# RightSide.net
KiCad netlist of a schematic drawn in Altium Designer
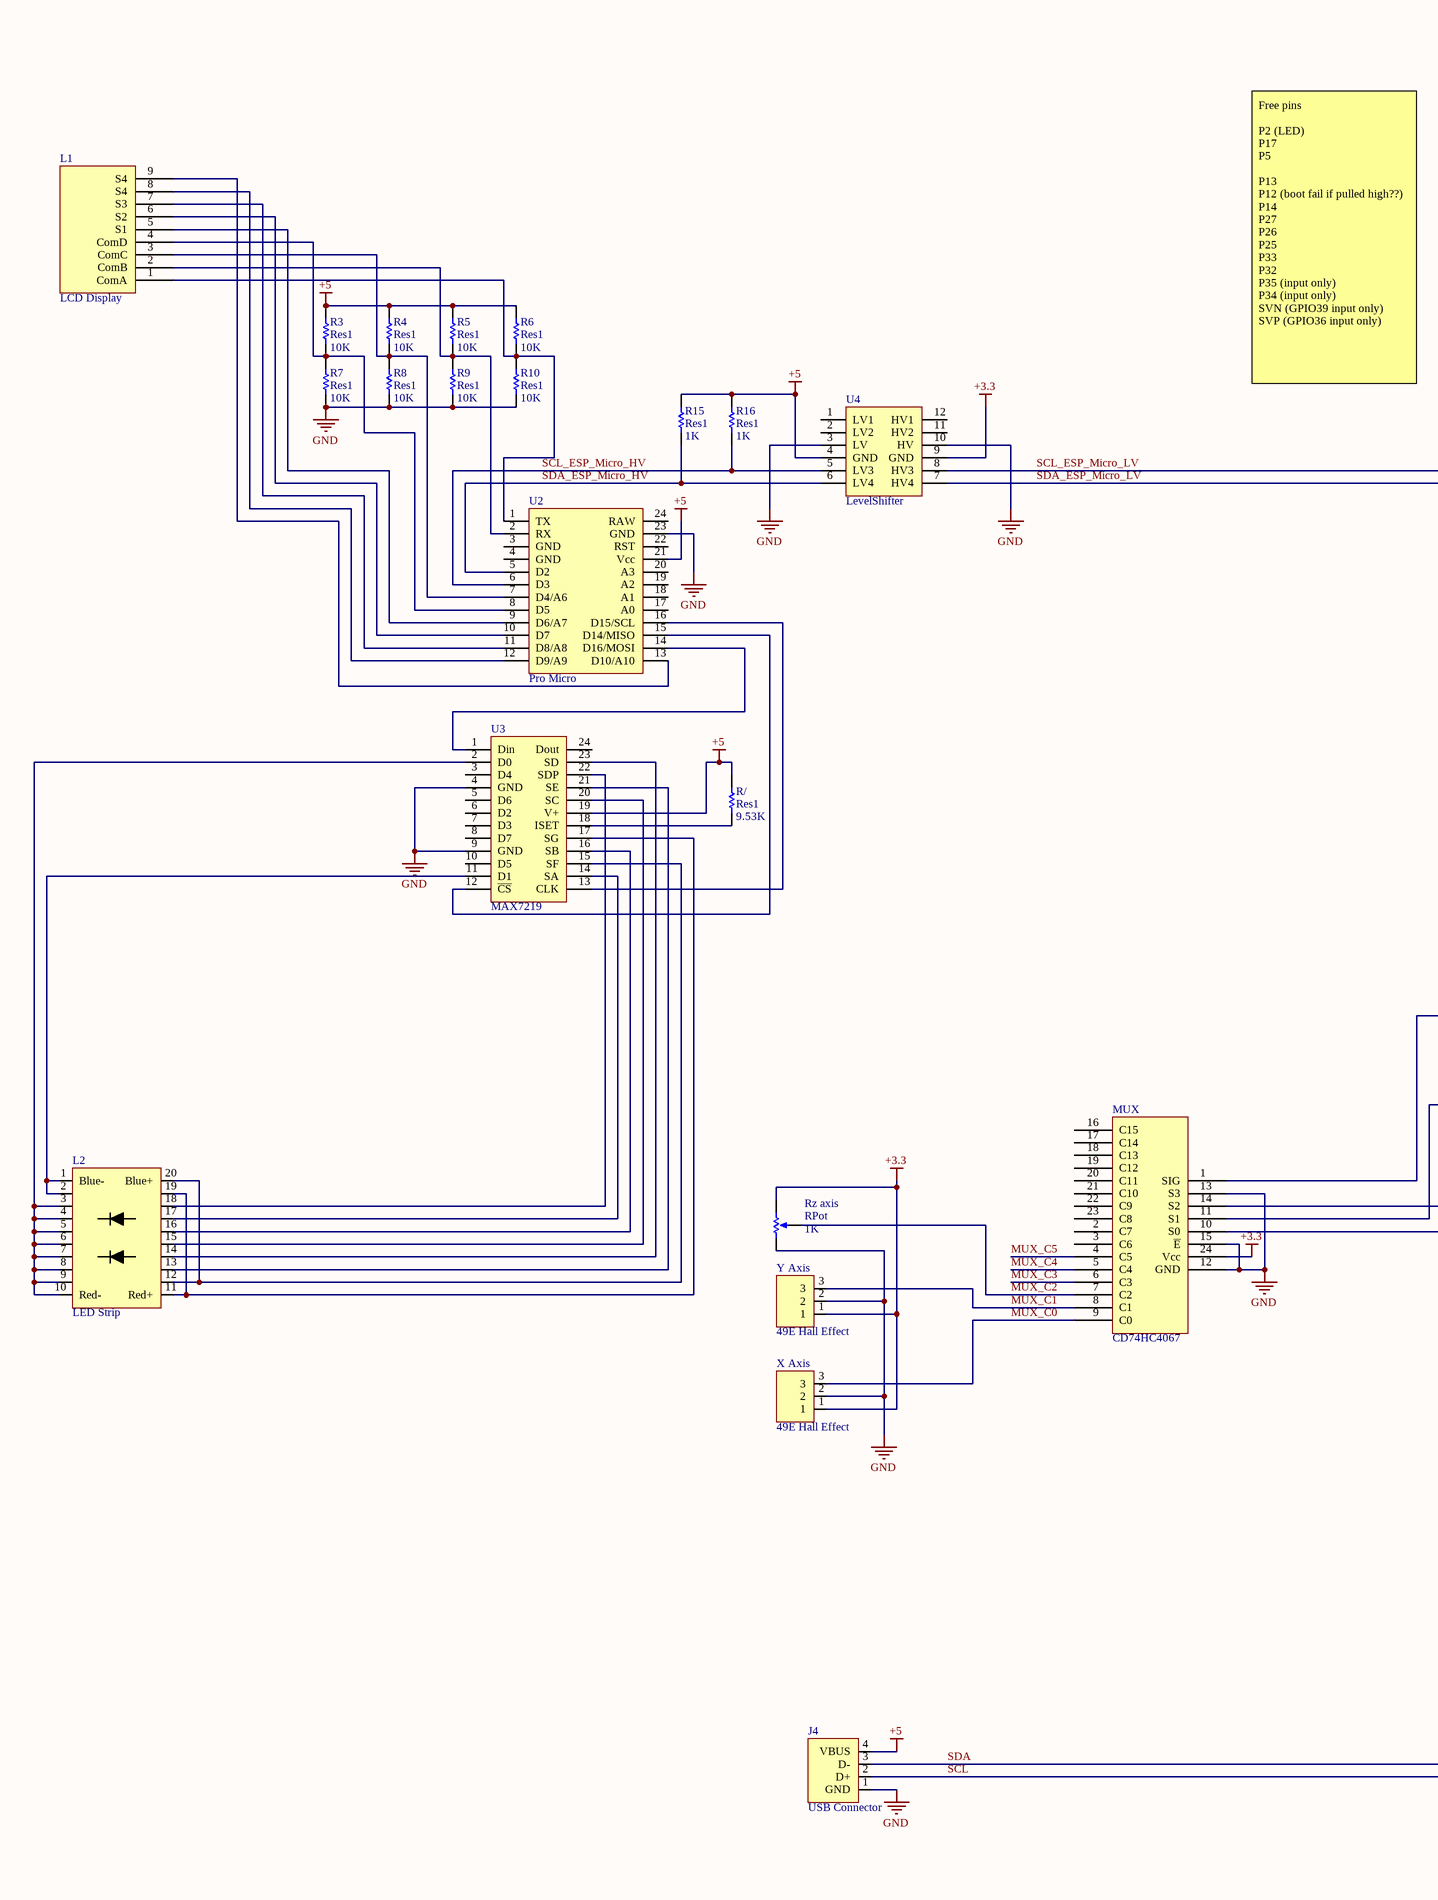
[diagram p0: RightSide.SchDoc, left]
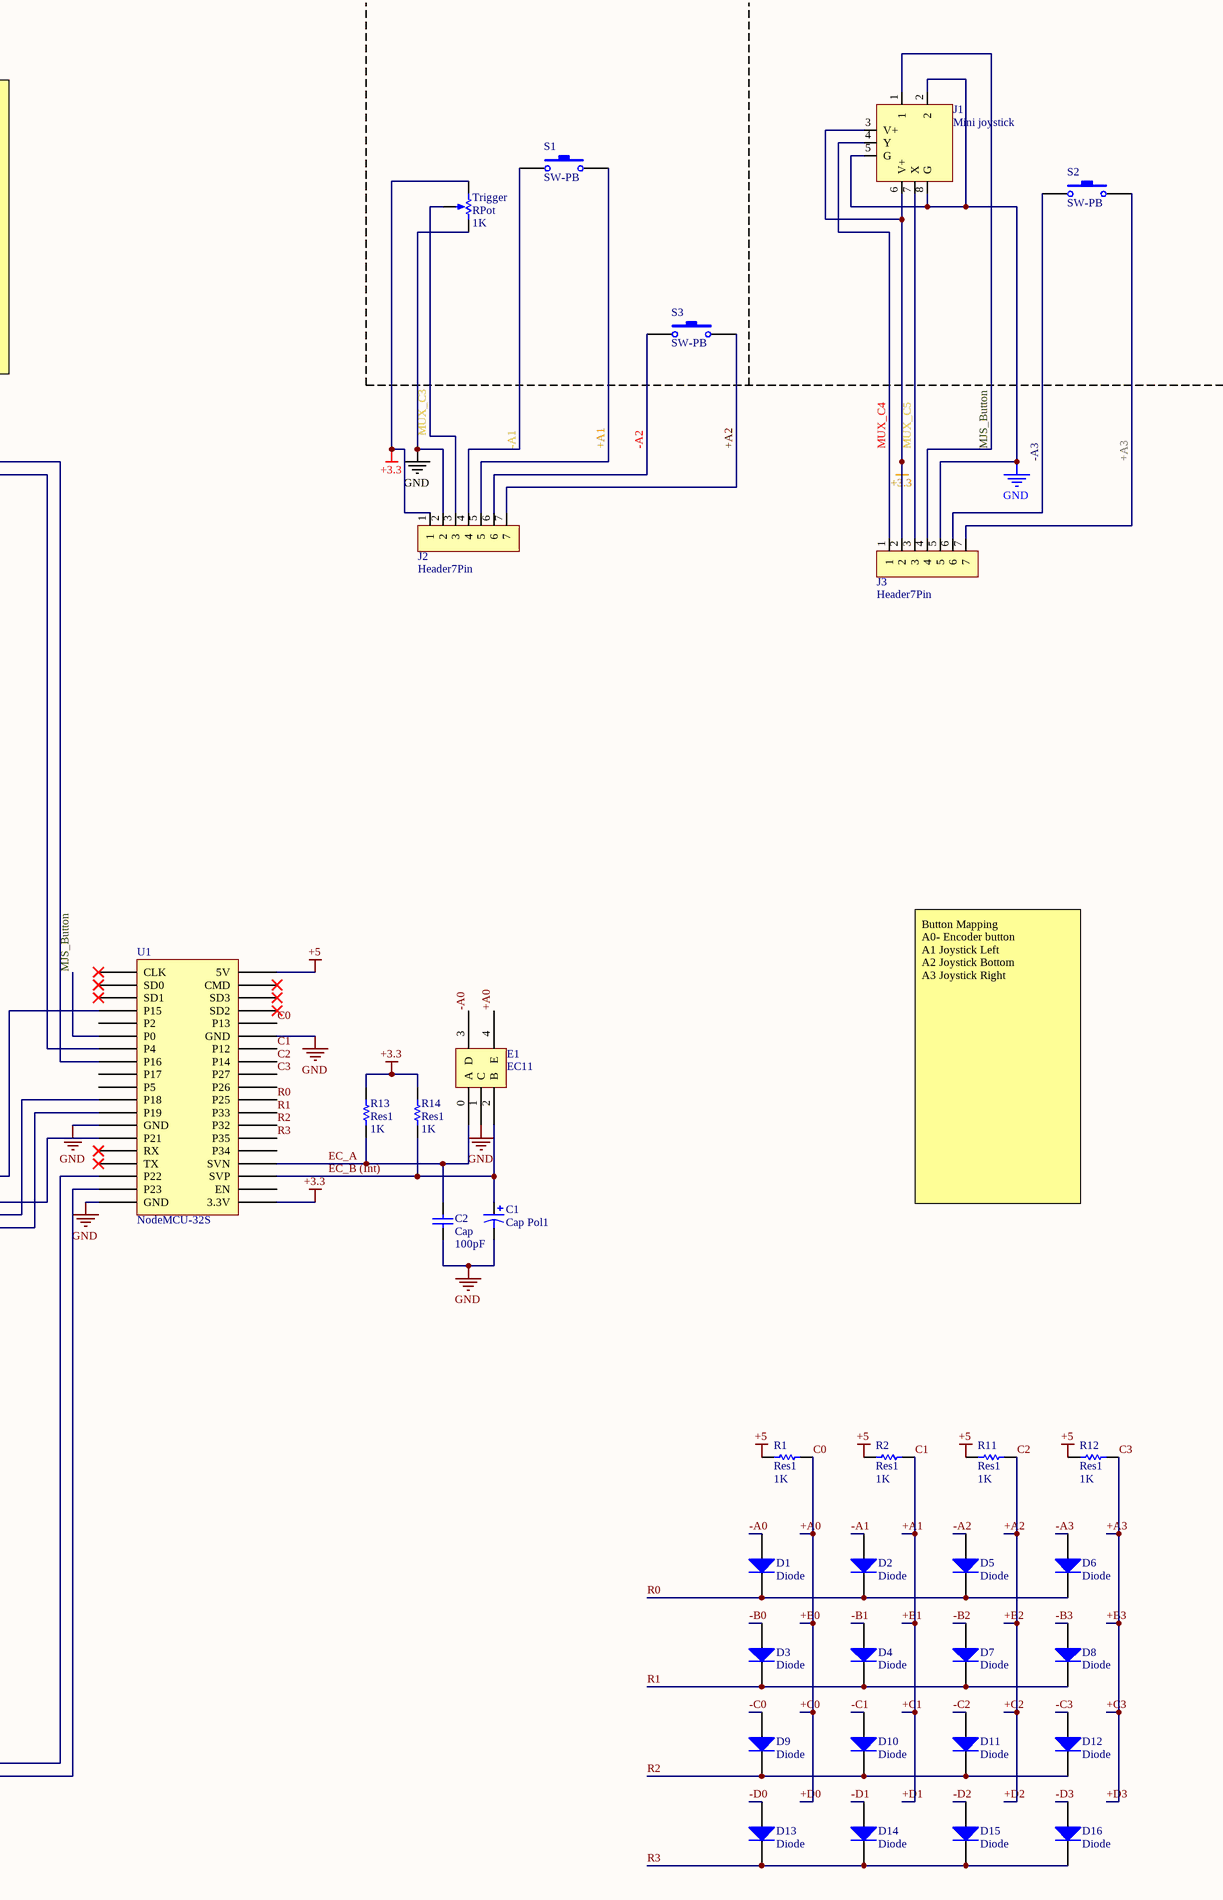
[diagram p1: RightSide.SchDoc, right]

(export (version "E")
  (design (tool "Eeschema 10.0.6"))
  (components
    (comp (ref "C1")
      (value "Cap Pol1")
      (footprint "RB7.6-15")
      (description "Polarized Capacitor (Radial)")
      (fields (field (name "PUBLISHER") "Altium Limited"))
      (libsource (lib "Miscellaneous Devices") (part "Cap Pol1"))
    )
    (comp (ref "C2")
      (value "Cap")
      (footprint "RAD-0.3")
      (description "Capacitor")
      (fields (field (name "ALTIUM_VALUE") "100pF") (field (name "PUBLISHER") "Altium Limited"))
      (libsource (lib "Miscellaneous Devices") (part "Cap"))
    )
    (comp (ref "D1")
      (value "Diode")
      (footprint "Diode_300mil")
      (description "Default Diode")
      (fields (field (name "PUBLISHER") "Altium Limited"))
      (libsource (lib "Miscellaneous Devices") (part "Diode"))
    )
    (comp (ref "D2")
      (value "Diode")
      (footprint "Diode_300mil")
      (description "Default Diode")
      (fields (field (name "PUBLISHER") "Altium Limited"))
      (libsource (lib "Miscellaneous Devices") (part "Diode"))
    )
    (comp (ref "D3")
      (value "Diode")
      (footprint "Diode_300mil")
      (description "Default Diode")
      (fields (field (name "PUBLISHER") "Altium Limited"))
      (libsource (lib "Miscellaneous Devices") (part "Diode"))
    )
    (comp (ref "D4")
      (value "Diode")
      (footprint "Diode_300mil")
      (description "Default Diode")
      (fields (field (name "PUBLISHER") "Altium Limited"))
      (libsource (lib "Miscellaneous Devices") (part "Diode"))
    )
    (comp (ref "D5")
      (value "Diode")
      (footprint "Diode_300mil")
      (description "Default Diode")
      (fields (field (name "PUBLISHER") "Altium Limited"))
      (libsource (lib "Miscellaneous Devices") (part "Diode"))
    )
    (comp (ref "D6")
      (value "Diode")
      (footprint "Diode_300mil")
      (description "Default Diode")
      (fields (field (name "PUBLISHER") "Altium Limited"))
      (libsource (lib "Miscellaneous Devices") (part "Diode"))
    )
    (comp (ref "D7")
      (value "Diode")
      (footprint "Diode_300mil")
      (description "Default Diode")
      (fields (field (name "PUBLISHER") "Altium Limited"))
      (libsource (lib "Miscellaneous Devices") (part "Diode"))
    )
    (comp (ref "D8")
      (value "Diode")
      (footprint "Diode_300mil")
      (description "Default Diode")
      (fields (field (name "PUBLISHER") "Altium Limited"))
      (libsource (lib "Miscellaneous Devices") (part "Diode"))
    )
    (comp (ref "D9")
      (value "Diode")
      (footprint "Diode_300mil")
      (description "Default Diode")
      (fields (field (name "PUBLISHER") "Altium Limited"))
      (libsource (lib "Miscellaneous Devices") (part "Diode"))
    )
    (comp (ref "D10")
      (value "Diode")
      (footprint "Diode_300mil")
      (description "Default Diode")
      (fields (field (name "PUBLISHER") "Altium Limited"))
      (libsource (lib "Miscellaneous Devices") (part "Diode"))
    )
    (comp (ref "D11")
      (value "Diode")
      (footprint "Diode_300mil")
      (description "Default Diode")
      (fields (field (name "PUBLISHER") "Altium Limited"))
      (libsource (lib "Miscellaneous Devices") (part "Diode"))
    )
    (comp (ref "D12")
      (value "Diode")
      (footprint "Diode_300mil")
      (description "Default Diode")
      (fields (field (name "PUBLISHER") "Altium Limited"))
      (libsource (lib "Miscellaneous Devices") (part "Diode"))
    )
    (comp (ref "D13")
      (value "Diode")
      (footprint "Diode_300mil")
      (description "Default Diode")
      (fields (field (name "PUBLISHER") "Altium Limited"))
      (libsource (lib "Miscellaneous Devices") (part "Diode"))
    )
    (comp (ref "D14")
      (value "Diode")
      (footprint "Diode_300mil")
      (description "Default Diode")
      (fields (field (name "PUBLISHER") "Altium Limited"))
      (libsource (lib "Miscellaneous Devices") (part "Diode"))
    )
    (comp (ref "D15")
      (value "Diode")
      (footprint "Diode_300mil")
      (description "Default Diode")
      (fields (field (name "PUBLISHER") "Altium Limited"))
      (libsource (lib "Miscellaneous Devices") (part "Diode"))
    )
    (comp (ref "D16")
      (value "Diode")
      (footprint "Diode_300mil")
      (description "Default Diode")
      (fields (field (name "PUBLISHER") "Altium Limited"))
      (libsource (lib "Miscellaneous Devices") (part "Diode"))
    )
    (comp (ref "E1")
      (value "EC11")
      (footprint "Encoder")
      (description "Rot Encoder\r\nC GND\r\nPull up A,B")
      (libsource (lib "PartsSchLib") (part "EC11"))
    )
    (comp (ref "J1")
      (value "Mini joystick")
      (footprint "MiniJoyStick")
      (libsource (lib "PartsSchLib") (part "Mini joystick"))
    )
    (comp (ref "J2")
      (value "Header7Pin")
      (footprint "Header7Pin")
      (libsource (lib "PartsSchLib") (part "Header7Pin"))
    )
    (comp (ref "J3")
      (value "Header7Pin")
      (footprint "Header7Pin")
      (libsource (lib "PartsSchLib") (part "Header7Pin"))
    )
    (comp (ref "J4")
      (value "USB Connector")
      (footprint "USB-B")
      (libsource (lib "PartsSchLib") (part "USB Connector"))
    )
    (comp (ref "L1")
      (value "LCD Display")
      (footprint "LCD Display")
      (libsource (lib "PartsSchLib") (part "LCD Display"))
    )
    (comp (ref "L2") (value "LED Strip") (libsource (lib "PartsSchLib") (part "LED Strip")))
    (comp (ref "MUX")
      (value "CD74HC4067")
      (footprint "CD74HC4067")
      (description "Analog Multiplexer")
      (libsource (lib "PartsSchLib") (part "CD74HC4067"))
    )
    (comp (ref "R/")
      (value "Res1")
      (footprint "AXIAL-0.3")
      (description "Resistor")
      (fields (field (name "ALTIUM_VALUE") "9.53K") (field (name "PUBLISHER") "Altium Limited"))
      (libsource (lib "Miscellaneous Devices") (part "Res1"))
    )
    (comp (ref "R1")
      (value "Res1")
      (footprint "AXIAL-0.3")
      (description "Resistor")
      (fields (field (name "ALTIUM_VALUE") "1K") (field (name "PUBLISHER") "Altium Limited"))
      (libsource (lib "Miscellaneous Devices") (part "Res1"))
    )
    (comp (ref "R2")
      (value "Res1")
      (footprint "AXIAL-0.3")
      (description "Resistor")
      (fields (field (name "ALTIUM_VALUE") "1K") (field (name "PUBLISHER") "Altium Limited"))
      (libsource (lib "Miscellaneous Devices") (part "Res1"))
    )
    (comp (ref "R3")
      (value "Res1")
      (footprint "AXIAL-0.3")
      (description "Resistor")
      (fields (field (name "ALTIUM_VALUE") "10K") (field (name "PUBLISHER") "Altium Limited"))
      (libsource (lib "Miscellaneous Devices") (part "Res1"))
    )
    (comp (ref "R4")
      (value "Res1")
      (footprint "AXIAL-0.3")
      (description "Resistor")
      (fields (field (name "ALTIUM_VALUE") "10K") (field (name "PUBLISHER") "Altium Limited"))
      (libsource (lib "Miscellaneous Devices") (part "Res1"))
    )
    (comp (ref "R5")
      (value "Res1")
      (footprint "AXIAL-0.3")
      (description "Resistor")
      (fields (field (name "ALTIUM_VALUE") "10K") (field (name "PUBLISHER") "Altium Limited"))
      (libsource (lib "Miscellaneous Devices") (part "Res1"))
    )
    (comp (ref "R6")
      (value "Res1")
      (footprint "AXIAL-0.3")
      (description "Resistor")
      (fields (field (name "ALTIUM_VALUE") "10K") (field (name "PUBLISHER") "Altium Limited"))
      (libsource (lib "Miscellaneous Devices") (part "Res1"))
    )
    (comp (ref "R7")
      (value "Res1")
      (footprint "AXIAL-0.3")
      (description "Resistor")
      (fields (field (name "ALTIUM_VALUE") "10K") (field (name "PUBLISHER") "Altium Limited"))
      (libsource (lib "Miscellaneous Devices") (part "Res1"))
    )
    (comp (ref "R8")
      (value "Res1")
      (footprint "AXIAL-0.3")
      (description "Resistor")
      (fields (field (name "ALTIUM_VALUE") "10K") (field (name "PUBLISHER") "Altium Limited"))
      (libsource (lib "Miscellaneous Devices") (part "Res1"))
    )
    (comp (ref "R9")
      (value "Res1")
      (footprint "AXIAL-0.3")
      (description "Resistor")
      (fields (field (name "ALTIUM_VALUE") "10K") (field (name "PUBLISHER") "Altium Limited"))
      (libsource (lib "Miscellaneous Devices") (part "Res1"))
    )
    (comp (ref "R10")
      (value "Res1")
      (footprint "AXIAL-0.3")
      (description "Resistor")
      (fields (field (name "ALTIUM_VALUE") "10K") (field (name "PUBLISHER") "Altium Limited"))
      (libsource (lib "Miscellaneous Devices") (part "Res1"))
    )
    (comp (ref "R11")
      (value "Res1")
      (footprint "AXIAL-0.3")
      (description "Resistor")
      (fields (field (name "ALTIUM_VALUE") "1K") (field (name "PUBLISHER") "Altium Limited"))
      (libsource (lib "Miscellaneous Devices") (part "Res1"))
    )
    (comp (ref "R12")
      (value "Res1")
      (footprint "AXIAL-0.3")
      (description "Resistor")
      (fields (field (name "ALTIUM_VALUE") "1K") (field (name "PUBLISHER") "Altium Limited"))
      (libsource (lib "Miscellaneous Devices") (part "Res1"))
    )
    (comp (ref "R13")
      (value "Res1")
      (footprint "AXIAL-0.3")
      (description "Resistor")
      (fields (field (name "ALTIUM_VALUE") "1K") (field (name "PUBLISHER") "Altium Limited"))
      (libsource (lib "Miscellaneous Devices") (part "Res1"))
    )
    (comp (ref "R14")
      (value "Res1")
      (footprint "AXIAL-0.3")
      (description "Resistor")
      (fields (field (name "ALTIUM_VALUE") "1K") (field (name "PUBLISHER") "Altium Limited"))
      (libsource (lib "Miscellaneous Devices") (part "Res1"))
    )
    (comp (ref "R15")
      (value "Res1")
      (footprint "AXIAL-0.3")
      (description "Resistor")
      (fields (field (name "ALTIUM_VALUE") "1K") (field (name "PUBLISHER") "Altium Limited"))
      (libsource (lib "Miscellaneous Devices") (part "Res1"))
    )
    (comp (ref "R16")
      (value "Res1")
      (footprint "AXIAL-0.3")
      (description "Resistor")
      (fields (field (name "ALTIUM_VALUE") "1K") (field (name "PUBLISHER") "Altium Limited"))
      (libsource (lib "Miscellaneous Devices") (part "Res1"))
    )
    (comp (ref "Rz axis")
      (value "RPot")
      (footprint "VR5")
      (description "Potentiometer")
      (fields (field (name "ALTIUM_VALUE") "1K") (field (name "PUBLISHER") "Altium Limited"))
      (libsource (lib "Miscellaneous Devices") (part "RPot"))
    )
    (comp (ref "S1")
      (value "SW-PB")
      (footprint "SPST-2")
      (description "Switch")
      (fields (field (name "PUBLISHER") "Altium Limited"))
      (libsource (lib "Miscellaneous Devices") (part "SW-PB"))
    )
    (comp (ref "S2")
      (value "SW-PB")
      (footprint "SPST-2")
      (description "Switch")
      (fields (field (name "PUBLISHER") "Altium Limited"))
      (libsource (lib "Miscellaneous Devices") (part "SW-PB"))
    )
    (comp (ref "S3")
      (value "SW-PB")
      (footprint "SPST-2")
      (description "Switch")
      (fields (field (name "PUBLISHER") "Altium Limited"))
      (libsource (lib "Miscellaneous Devices") (part "SW-PB"))
    )
    (comp (ref "Trigger")
      (value "RPot")
      (footprint "VR5")
      (description "Potentiometer")
      (fields (field (name "ALTIUM_VALUE") "1K") (field (name "PUBLISHER") "Altium Limited"))
      (libsource (lib "Miscellaneous Devices") (part "RPot"))
    )
    (comp (ref "U1")
      (value "NodeMCU-32S")
      (footprint "DIP38")
      (libsource (lib "PartsSchLib") (part "NodeMCU-32S"))
    )
    (comp (ref "U2")
      (value "Pro Micro")
      (footprint "DIP24 x 600mil")
      (libsource (lib "PartsSchLib") (part "Pro Micro"))
    )
    (comp (ref "U3")
      (value "MAX7219")
      (footprint "DIP24 x 300mil")
      (description "https://datasheets.maximintegrated.com/en/ds/MAX7219-MAX7221.pdf")
      (libsource (lib "PartsSchLib") (part "MAX7219"))
    )
    (comp (ref "U4")
      (value "LevelShifter")
      (footprint "LevelShifter")
      (libsource (lib "PartsSchLib") (part "LevelShifter"))
    )
    (comp (ref "X Axis") (value "49E Hall Effect") (libsource (lib "PartsSchLib") (part "49E Hall Effect")))
    (comp (ref "Y Axis") (value "49E Hall Effect") (libsource (lib "PartsSchLib") (part "49E Hall Effect")))
  )
  (nets
    (net (code "1") (name "+3.3") (class "Default")
      (node (ref "J1") (pin "3") (pinfunction "V+_3") (pintype "passive"))
      (node (ref "J1") (pin "6") (pinfunction "V+_6") (pintype "passive"))
      (node (ref "J2") (pin "1") (pinfunction "1_1") (pintype "passive"))
      (node (ref "J3") (pin "2") (pinfunction "2_2") (pintype "passive"))
      (node (ref "MUX") (pin "24") (pinfunction "Vcc_24") (pintype "passive"))
      (node (ref "R13") (pin "2") (pinfunction "2_2") (pintype "passive"))
      (node (ref "R14") (pin "2") (pinfunction "2_2") (pintype "passive"))
      (node (ref "Rz axis") (pin "2") (pinfunction "BOT_2") (pintype "passive"))
      (node (ref "Trigger") (pin "1") (pinfunction "TOP_1") (pintype "passive"))
      (node (ref "U1") (pin "20") (pinfunction "3.3V_20") (pintype "passive"))
      (node (ref "U4") (pin "9") (pinfunction "GND_9") (pintype "passive"))
      (node (ref "X Axis") (pin "1") (pinfunction "1_1") (pintype "passive"))
      (node (ref "Y Axis") (pin "1") (pinfunction "1_1") (pintype "passive"))
    )
    (net (code "2") (name "+5") (class "Default")
      (node (ref "J4") (pin "4") (pinfunction "VBUS_4") (pintype "passive"))
      (node (ref "R/") (pin "2") (pinfunction "2_2") (pintype "passive"))
      (node (ref "R1") (pin "1") (pinfunction "1_1") (pintype "passive"))
      (node (ref "R11") (pin "1") (pinfunction "1_1") (pintype "passive"))
      (node (ref "R12") (pin "1") (pinfunction "1_1") (pintype "passive"))
      (node (ref "R15") (pin "2") (pinfunction "2_2") (pintype "passive"))
      (node (ref "R16") (pin "2") (pinfunction "2_2") (pintype "passive"))
      (node (ref "R2") (pin "1") (pinfunction "1_1") (pintype "passive"))
      (node (ref "R3") (pin "2") (pinfunction "2_2") (pintype "passive"))
      (node (ref "R4") (pin "2") (pinfunction "2_2") (pintype "passive"))
      (node (ref "R5") (pin "2") (pinfunction "2_2") (pintype "passive"))
      (node (ref "R6") (pin "2") (pinfunction "2_2") (pintype "passive"))
      (node (ref "U1") (pin "38") (pinfunction "5V_38") (pintype "passive"))
      (node (ref "U2") (pin "21") (pinfunction "Vcc_21") (pintype "passive"))
      (node (ref "U3") (pin "19") (pinfunction "V+_19") (pintype "passive"))
      (node (ref "U4") (pin "4") (pinfunction "GND_4") (pintype "passive"))
    )
    (net (code "3") (name "/+A0") (class "Default")
      (node (ref "E1") (pin "4") (pinfunction "E_4") (pintype "passive"))
      (node (ref "R1") (pin "2") (pinfunction "2_2") (pintype "passive"))
      (node (ref "U1") (pin "34") (pinfunction "P13_34") (pintype "passive"))
    )
    (net (code "4") (name "/+A1") (class "Default")
      (node (ref "J2") (pin "5") (pinfunction "5_5") (pintype "passive"))
      (node (ref "R2") (pin "2") (pinfunction "2_2") (pintype "passive"))
      (node (ref "S1") (pin "2") (pinfunction "2_2") (pintype "passive"))
      (node (ref "U1") (pin "32") (pinfunction "P12_32") (pintype "passive"))
    )
    (net (code "5") (name "/+A2") (class "Default")
      (node (ref "J2") (pin "7") (pinfunction "7_7") (pintype "passive"))
      (node (ref "R11") (pin "2") (pinfunction "2_2") (pintype "passive"))
      (node (ref "S3") (pin "2") (pinfunction "2_2") (pintype "passive"))
      (node (ref "U1") (pin "31") (pinfunction "P14_31") (pintype "passive"))
    )
    (net (code "6") (name "/+A3") (class "Default")
      (node (ref "J3") (pin "7") (pinfunction "7_7") (pintype "passive"))
      (node (ref "R12") (pin "2") (pinfunction "2_2") (pintype "passive"))
      (node (ref "S2") (pin "2") (pinfunction "2_2") (pintype "passive"))
      (node (ref "U1") (pin "30") (pinfunction "P27_30") (pintype "passive"))
    )
    (net (code "7") (name "/-A0") (class "Default")
      (node (ref "D1") (pin "1") (pinfunction "A_1") (pintype "passive"))
      (node (ref "E1") (pin "3") (pinfunction "D_3") (pintype "passive"))
    )
    (net (code "8") (name "/-A1") (class "Default")
      (node (ref "D2") (pin "1") (pinfunction "A_1") (pintype "passive"))
      (node (ref "J2") (pin "4") (pinfunction "4_4") (pintype "passive"))
      (node (ref "S1") (pin "1") (pinfunction "1_1") (pintype "passive"))
    )
    (net (code "9") (name "/-A2") (class "Default")
      (node (ref "D5") (pin "1") (pinfunction "A_1") (pintype "passive"))
      (node (ref "J2") (pin "6") (pinfunction "6_6") (pintype "passive"))
      (node (ref "S3") (pin "1") (pinfunction "1_1") (pintype "passive"))
    )
    (net (code "10") (name "/-A3") (class "Default")
      (node (ref "D6") (pin "1") (pinfunction "A_1") (pintype "passive"))
      (node (ref "J3") (pin "6") (pinfunction "6_6") (pintype "passive"))
      (node (ref "S2") (pin "1") (pinfunction "1_1") (pintype "passive"))
    )
    (net (code "11") (name "/-B0") (class "Default")
      (node (ref "D3") (pin "1") (pinfunction "A_1") (pintype "passive"))
    )
    (net (code "12") (name "/-B1") (class "Default")
      (node (ref "D4") (pin "1") (pinfunction "A_1") (pintype "passive"))
    )
    (net (code "13") (name "/-B2") (class "Default")
      (node (ref "D7") (pin "1") (pinfunction "A_1") (pintype "passive"))
    )
    (net (code "14") (name "/-B3") (class "Default")
      (node (ref "D8") (pin "1") (pinfunction "A_1") (pintype "passive"))
    )
    (net (code "15") (name "/-C0") (class "Default")
      (node (ref "D9") (pin "1") (pinfunction "A_1") (pintype "passive"))
    )
    (net (code "16") (name "/-C1") (class "Default")
      (node (ref "D10") (pin "1") (pinfunction "A_1") (pintype "passive"))
    )
    (net (code "17") (name "/-C2") (class "Default")
      (node (ref "D11") (pin "1") (pinfunction "A_1") (pintype "passive"))
    )
    (net (code "18") (name "/-C3") (class "Default")
      (node (ref "D12") (pin "1") (pinfunction "A_1") (pintype "passive"))
    )
    (net (code "19") (name "/-D0") (class "Default")
      (node (ref "D13") (pin "1") (pinfunction "A_1") (pintype "passive"))
    )
    (net (code "20") (name "/-D1") (class "Default")
      (node (ref "D14") (pin "1") (pinfunction "A_1") (pintype "passive"))
    )
    (net (code "21") (name "/-D2") (class "Default")
      (node (ref "D15") (pin "1") (pinfunction "A_1") (pintype "passive"))
    )
    (net (code "22") (name "/-D3") (class "Default")
      (node (ref "D16") (pin "1") (pinfunction "A_1") (pintype "passive"))
    )
    (net (code "23") (name "/EC_A") (class "Default")
      (node (ref "C2") (pin "2") (pinfunction "2_2") (pintype "passive"))
      (node (ref "E1") (pin "0") (pinfunction "A_0") (pintype "passive"))
      (node (ref "R13") (pin "1") (pinfunction "1_1") (pintype "passive"))
      (node (ref "U1") (pin "23") (pinfunction "SVN_23") (pintype "passive"))
    )
    (net (code "24") (name "/EC_B (Int)") (class "Default")
      (node (ref "C1") (pin "1") (pinfunction "1_1") (pintype "passive"))
      (node (ref "E1") (pin "2") (pinfunction "B_2") (pintype "passive"))
      (node (ref "R14") (pin "1") (pinfunction "1_1") (pintype "passive"))
      (node (ref "U1") (pin "22") (pinfunction "SVP_22") (pintype "passive"))
    )
    (net (code "25") (name "/MJS_Button") (class "Default")
      (node (ref "J1") (pin "1") (pinfunction "1_1") (pintype "passive"))
      (node (ref "J3") (pin "4") (pinfunction "4_4") (pintype "passive"))
      (node (ref "U1") (pin "6") (pinfunction "P0_6") (pintype "passive"))
    )
    (net (code "26") (name "/MUX_C0") (class "Default")
      (node (ref "MUX") (pin "9") (pinfunction "C0_9") (pintype "passive"))
      (node (ref "X Axis") (pin "3") (pinfunction "3_3") (pintype "passive"))
    )
    (net (code "27") (name "/MUX_C1") (class "Default")
      (node (ref "MUX") (pin "8") (pinfunction "C1_8") (pintype "passive"))
      (node (ref "Y Axis") (pin "3") (pinfunction "3_3") (pintype "passive"))
    )
    (net (code "28") (name "/MUX_C2") (class "Default")
      (node (ref "MUX") (pin "7") (pinfunction "C2_7") (pintype "passive"))
      (node (ref "Rz axis") (pin "3") (pinfunction "TAP_3") (pintype "passive"))
    )
    (net (code "29") (name "/MUX_C3") (class "Default")
      (node (ref "J2") (pin "3") (pinfunction "3_3") (pintype "passive"))
      (node (ref "MUX") (pin "6") (pinfunction "C3_6") (pintype "passive"))
      (node (ref "Trigger") (pin "3") (pinfunction "TAP_3") (pintype "passive"))
    )
    (net (code "30") (name "/MUX_C4") (class "Default")
      (node (ref "J1") (pin "4") (pinfunction "Y_4") (pintype "passive"))
      (node (ref "J3") (pin "1") (pinfunction "1_1") (pintype "passive"))
      (node (ref "MUX") (pin "5") (pinfunction "C4_5") (pintype "passive"))
    )
    (net (code "31") (name "/MUX_C5") (class "Default")
      (node (ref "J1") (pin "7") (pinfunction "X_7") (pintype "passive"))
      (node (ref "J3") (pin "3") (pinfunction "3_3") (pintype "passive"))
      (node (ref "MUX") (pin "4") (pinfunction "C5_4") (pintype "passive"))
    )
    (net (code "32") (name "/R0") (class "Default")
      (node (ref "D1") (pin "2") (pinfunction "K_2") (pintype "passive"))
      (node (ref "D2") (pin "2") (pinfunction "K_2") (pintype "passive"))
      (node (ref "D5") (pin "2") (pinfunction "K_2") (pintype "passive"))
      (node (ref "D6") (pin "2") (pinfunction "K_2") (pintype "passive"))
      (node (ref "U1") (pin "28") (pinfunction "P25_28") (pintype "passive"))
    )
    (net (code "33") (name "/R1") (class "Default")
      (node (ref "D3") (pin "2") (pinfunction "K_2") (pintype "passive"))
      (node (ref "D4") (pin "2") (pinfunction "K_2") (pintype "passive"))
      (node (ref "D7") (pin "2") (pinfunction "K_2") (pintype "passive"))
      (node (ref "D8") (pin "2") (pinfunction "K_2") (pintype "passive"))
      (node (ref "U1") (pin "27") (pinfunction "P33_27") (pintype "passive"))
    )
    (net (code "34") (name "/R2") (class "Default")
      (node (ref "D10") (pin "2") (pinfunction "K_2") (pintype "passive"))
      (node (ref "D11") (pin "2") (pinfunction "K_2") (pintype "passive"))
      (node (ref "D12") (pin "2") (pinfunction "K_2") (pintype "passive"))
      (node (ref "D9") (pin "2") (pinfunction "K_2") (pintype "passive"))
      (node (ref "U1") (pin "26") (pinfunction "P32_26") (pintype "passive"))
    )
    (net (code "35") (name "/R3") (class "Default")
      (node (ref "D13") (pin "2") (pinfunction "K_2") (pintype "passive"))
      (node (ref "D14") (pin "2") (pinfunction "K_2") (pintype "passive"))
      (node (ref "D15") (pin "2") (pinfunction "K_2") (pintype "passive"))
      (node (ref "D16") (pin "2") (pinfunction "K_2") (pintype "passive"))
      (node (ref "U1") (pin "25") (pinfunction "P35_25") (pintype "passive"))
    )
    (net (code "36") (name "/SCL") (class "Default")
      (node (ref "J4") (pin "2") (pinfunction "D+_2") (pintype "passive"))
      (node (ref "U1") (pin "18") (pinfunction "P23_18") (pintype "passive"))
    )
    (net (code "37") (name "/SCL_ESP_Micro_HV") (class "Default")
      (node (ref "R16") (pin "1") (pinfunction "1_1") (pintype "passive"))
      (node (ref "U2") (pin "6") (pinfunction "D3_6") (pintype "passive"))
      (node (ref "U4") (pin "5") (pinfunction "LV3_5") (pintype "passive"))
    )
    (net (code "38") (name "/SCL_ESP_Micro_LV") (class "Default")
      (node (ref "U1") (pin "8") (pinfunction "P16_8") (pintype "passive"))
      (node (ref "U4") (pin "8") (pinfunction "HV3_8") (pintype "passive"))
    )
    (net (code "39") (name "/SDA") (class "Default")
      (node (ref "J4") (pin "3") (pinfunction "D-_3") (pintype "passive"))
      (node (ref "U1") (pin "17") (pinfunction "P22_17") (pintype "passive"))
    )
    (net (code "40") (name "/SDA_ESP_Micro_HV") (class "Default")
      (node (ref "R15") (pin "1") (pinfunction "1_1") (pintype "passive"))
      (node (ref "U2") (pin "5") (pinfunction "D2_5") (pintype "passive"))
      (node (ref "U4") (pin "6") (pinfunction "LV4_6") (pintype "passive"))
    )
    (net (code "41") (name "/SDA_ESP_Micro_LV") (class "Default")
      (node (ref "U1") (pin "7") (pinfunction "P4_7") (pintype "passive"))
      (node (ref "U4") (pin "7") (pinfunction "HV4_7") (pintype "passive"))
    )
    (net (code "42") (name "GND") (class "Default")
      (node (ref "C1") (pin "2") (pinfunction "2_2") (pintype "passive"))
      (node (ref "C2") (pin "1") (pinfunction "1_1") (pintype "passive"))
      (node (ref "E1") (pin "1") (pinfunction "C_1") (pintype "passive"))
      (node (ref "J1") (pin "2") (pinfunction "2_2") (pintype "passive"))
      (node (ref "J1") (pin "5") (pinfunction "G_5") (pintype "passive"))
      (node (ref "J1") (pin "8") (pinfunction "G_8") (pintype "passive"))
      (node (ref "J2") (pin "2") (pinfunction "2_2") (pintype "passive"))
      (node (ref "J3") (pin "5") (pinfunction "5_5") (pintype "passive"))
      (node (ref "J4") (pin "1") (pinfunction "GND_1") (pintype "passive"))
      (node (ref "MUX") (pin "12") (pinfunction "GND_12") (pintype "passive"))
      (node (ref "MUX") (pin "13") (pinfunction "S3_13") (pintype "passive"))
      (node (ref "MUX") (pin "15") (pinfunction "~{E}_15") (pintype "passive"))
      (node (ref "R10") (pin "1") (pinfunction "1_1") (pintype "passive"))
      (node (ref "R7") (pin "1") (pinfunction "1_1") (pintype "passive"))
      (node (ref "R8") (pin "1") (pinfunction "1_1") (pintype "passive"))
      (node (ref "R9") (pin "1") (pinfunction "1_1") (pintype "passive"))
      (node (ref "Rz axis") (pin "1") (pinfunction "TOP_1") (pintype "passive"))
      (node (ref "Trigger") (pin "2") (pinfunction "BOT_2") (pintype "passive"))
      (node (ref "U1") (pin "13") (pinfunction "GND_13") (pintype "passive"))
      (node (ref "U1") (pin "19") (pinfunction "GND_19") (pintype "passive"))
      (node (ref "U1") (pin "33") (pinfunction "GND_33") (pintype "passive"))
      (node (ref "U2") (pin "23") (pinfunction "GND_23") (pintype "passive"))
      (node (ref "U3") (pin "4") (pinfunction "GND_4") (pintype "passive"))
      (node (ref "U3") (pin "9") (pinfunction "GND_9") (pintype "passive"))
      (node (ref "U4") (pin "10") (pinfunction "HV_10") (pintype "passive"))
      (node (ref "U4") (pin "3") (pinfunction "LV_3") (pintype "passive"))
      (node (ref "X Axis") (pin "2") (pinfunction "2_2") (pintype "passive"))
      (node (ref "Y Axis") (pin "2") (pinfunction "2_2") (pintype "passive"))
    )
    (net (code "43") (name "Net-(L1-ComA)") (class "Default")
      (node (ref "L1") (pin "1") (pinfunction "ComA_1") (pintype "passive"))
      (node (ref "R10") (pin "2") (pinfunction "2_2") (pintype "passive"))
      (node (ref "R6") (pin "1") (pinfunction "1_1") (pintype "passive"))
      (node (ref "U2") (pin "1") (pinfunction "TX_1") (pintype "passive"))
    )
    (net (code "44") (name "Net-(L1-ComB)") (class "Default")
      (node (ref "L1") (pin "2") (pinfunction "ComB_2") (pintype "passive"))
      (node (ref "R5") (pin "1") (pinfunction "1_1") (pintype "passive"))
      (node (ref "R9") (pin "2") (pinfunction "2_2") (pintype "passive"))
      (node (ref "U2") (pin "2") (pinfunction "RX_2") (pintype "passive"))
    )
    (net (code "45") (name "Net-(L1-ComC)") (class "Default")
      (node (ref "L1") (pin "3") (pinfunction "ComC_3") (pintype "passive"))
      (node (ref "R4") (pin "1") (pinfunction "1_1") (pintype "passive"))
      (node (ref "R8") (pin "2") (pinfunction "2_2") (pintype "passive"))
      (node (ref "U2") (pin "7") (pinfunction "D4/A6_7") (pintype "passive"))
    )
    (net (code "46") (name "Net-(L1-ComD)") (class "Default")
      (node (ref "L1") (pin "4") (pinfunction "ComD_4") (pintype "passive"))
      (node (ref "R3") (pin "1") (pinfunction "1_1") (pintype "passive"))
      (node (ref "R7") (pin "2") (pinfunction "2_2") (pintype "passive"))
      (node (ref "U2") (pin "8") (pinfunction "D5_8") (pintype "passive"))
    )
    (net (code "47") (name "Net-(L1-S1)") (class "Default")
      (node (ref "L1") (pin "5") (pinfunction "S1_5") (pintype "passive"))
      (node (ref "U2") (pin "9") (pinfunction "D6/A7_9") (pintype "passive"))
    )
    (net (code "48") (name "Net-(L1-S2)") (class "Default")
      (node (ref "L1") (pin "6") (pinfunction "S2_6") (pintype "passive"))
      (node (ref "U2") (pin "10") (pinfunction "D7_10") (pintype "passive"))
    )
    (net (code "49") (name "Net-(L1-S3)") (class "Default")
      (node (ref "L1") (pin "7") (pinfunction "S3_7") (pintype "passive"))
      (node (ref "U2") (pin "11") (pinfunction "D8/A8_11") (pintype "passive"))
    )
    (net (code "50") (name "Net-(L2-Blue+)") (class "Default")
      (node (ref "L2") (pin "12") (pintype "passive"))
      (node (ref "L2") (pin "20") (pinfunction "Blue+_20") (pintype "passive"))
      (node (ref "U3") (pin "15") (pinfunction "SF_15") (pintype "passive"))
    )
    (net (code "51") (name "Net-(L2-Blue-)") (class "Default")
      (node (ref "L2") (pin "1") (pinfunction "Blue-_1") (pintype "passive"))
      (node (ref "L2") (pin "2") (pintype "passive"))
      (node (ref "U3") (pin "11") (pinfunction "D1_11") (pintype "passive"))
    )
    (net (code "52") (name "Net-(L2-Red+)") (class "Default")
      (node (ref "L2") (pin "11") (pinfunction "Red+_11") (pintype "passive"))
      (node (ref "L2") (pin "19") (pintype "passive"))
      (node (ref "U3") (pin "17") (pinfunction "SG_17") (pintype "passive"))
    )
    (net (code "53") (name "Net-(L2-Red-)") (class "Default")
      (node (ref "L2") (pin "10") (pinfunction "Red-_10") (pintype "passive"))
      (node (ref "L2") (pin "3") (pintype "passive"))
      (node (ref "L2") (pin "4") (pintype "passive"))
      (node (ref "L2") (pin "5") (pintype "passive"))
      (node (ref "L2") (pin "6") (pintype "passive"))
      (node (ref "L2") (pin "7") (pintype "passive"))
      (node (ref "L2") (pin "8") (pintype "passive"))
      (node (ref "L2") (pin "9") (pintype "passive"))
      (node (ref "U3") (pin "2") (pinfunction "D0_2") (pintype "passive"))
    )
    (net (code "54") (name "Net-(MUX-S0)") (class "Default")
      (node (ref "MUX") (pin "10") (pinfunction "S0_10") (pintype "passive"))
      (node (ref "U1") (pin "12") (pinfunction "P19_12") (pintype "passive"))
    )
    (net (code "55") (name "Net-(MUX-S1)") (class "Default")
      (node (ref "MUX") (pin "11") (pinfunction "S1_11") (pintype "passive"))
      (node (ref "U1") (pin "11") (pinfunction "P18_11") (pintype "passive"))
    )
    (net (code "56") (name "Net-(MUX-S2)") (class "Default")
      (node (ref "MUX") (pin "14") (pinfunction "S2_14") (pintype "passive"))
      (node (ref "U1") (pin "14") (pinfunction "P21_14") (pintype "passive"))
    )
    (net (code "57") (name "Net-(MUX-SIG)") (class "Default")
      (node (ref "MUX") (pin "1") (pinfunction "SIG_1") (pintype "passive"))
      (node (ref "U1") (pin "4") (pinfunction "P15_4") (pintype "passive"))
    )
    (net (code "58") (name "Net-(U2-D9{slash}A9)") (class "Default")
      (node (ref "L1") (pin "8") (pinfunction "S4_8") (pintype "passive"))
      (node (ref "U2") (pin "12") (pinfunction "D9/A9_12") (pintype "passive"))
    )
    (net (code "59") (name "Net-(U2-D10{slash}A10)") (class "Default")
      (node (ref "L1") (pin "9") (pinfunction "S4_9") (pintype "passive"))
      (node (ref "U2") (pin "13") (pinfunction "D10/A10_13") (pintype "passive"))
    )
    (net (code "60") (name "Net-(U2-D14{slash}MISO)") (class "Default")
      (node (ref "U2") (pin "15") (pinfunction "D14/MISO_15") (pintype "passive"))
      (node (ref "U3") (pin "12") (pinfunction "~{CS}_12") (pintype "passive"))
    )
    (net (code "61") (name "Net-(U2-D15{slash}SCL)") (class "Default")
      (node (ref "U2") (pin "16") (pinfunction "D15/SCL_16") (pintype "passive"))
      (node (ref "U3") (pin "13") (pinfunction "CLK_13") (pintype "passive"))
    )
    (net (code "62") (name "Net-(U2-D16{slash}MOSI)") (class "Default")
      (node (ref "U2") (pin "14") (pinfunction "D16/MOSI_14") (pintype "passive"))
      (node (ref "U3") (pin "1") (pinfunction "Din_1") (pintype "passive"))
    )
    (net (code "63") (name "Net-(U3-ISET)") (class "Default")
      (node (ref "R/") (pin "1") (pinfunction "1_1") (pintype "passive"))
      (node (ref "U3") (pin "18") (pinfunction "ISET_18") (pintype "passive"))
    )
    (net (code "64") (name "Net-(U3-SA)") (class "Default")
      (node (ref "L2") (pin "17") (pintype "passive"))
      (node (ref "U3") (pin "14") (pinfunction "SA_14") (pintype "passive"))
    )
    (net (code "65") (name "Net-(U3-SB)") (class "Default")
      (node (ref "L2") (pin "16") (pintype "passive"))
      (node (ref "U3") (pin "16") (pinfunction "SB_16") (pintype "passive"))
    )
    (net (code "66") (name "Net-(U3-SC)") (class "Default")
      (node (ref "L2") (pin "15") (pintype "passive"))
      (node (ref "U3") (pin "20") (pinfunction "SC_20") (pintype "passive"))
    )
    (net (code "67") (name "Net-(U3-SD)") (class "Default")
      (node (ref "L2") (pin "14") (pintype "passive"))
      (node (ref "U3") (pin "23") (pinfunction "SD_23") (pintype "passive"))
    )
    (net (code "68") (name "Net-(U3-SDP)") (class "Default")
      (node (ref "L2") (pin "18") (pintype "passive"))
      (node (ref "U3") (pin "22") (pinfunction "SDP_22") (pintype "passive"))
    )
    (net (code "69") (name "Net-(U3-SE)") (class "Default")
      (node (ref "L2") (pin "13") (pintype "passive"))
      (node (ref "U3") (pin "21") (pinfunction "SE_21") (pintype "passive"))
    )
    (net (code "70") (name "unconnected-(MUX-C6-Pad3)") (class "Default")
      (node (ref "MUX") (pin "3") (pinfunction "C6_3") (pintype "passive"))
    )
    (net (code "71") (name "unconnected-(MUX-C7-Pad2)") (class "Default")
      (node (ref "MUX") (pin "2") (pinfunction "C7_2") (pintype "passive"))
    )
    (net (code "72") (name "unconnected-(MUX-C8-Pad23)") (class "Default")
      (node (ref "MUX") (pin "23") (pinfunction "C8_23") (pintype "passive"))
    )
    (net (code "73") (name "unconnected-(MUX-C9-Pad22)") (class "Default")
      (node (ref "MUX") (pin "22") (pinfunction "C9_22") (pintype "passive"))
    )
    (net (code "74") (name "unconnected-(MUX-C10-Pad21)") (class "Default")
      (node (ref "MUX") (pin "21") (pinfunction "C10_21") (pintype "passive"))
    )
    (net (code "75") (name "unconnected-(MUX-C11-Pad20)") (class "Default")
      (node (ref "MUX") (pin "20") (pinfunction "C11_20") (pintype "passive"))
    )
    (net (code "76") (name "unconnected-(MUX-C12-Pad19)") (class "Default")
      (node (ref "MUX") (pin "19") (pinfunction "C12_19") (pintype "passive"))
    )
    (net (code "77") (name "unconnected-(MUX-C13-Pad18)") (class "Default")
      (node (ref "MUX") (pin "18") (pinfunction "C13_18") (pintype "passive"))
    )
    (net (code "78") (name "unconnected-(MUX-C14-Pad17)") (class "Default")
      (node (ref "MUX") (pin "17") (pinfunction "C14_17") (pintype "passive"))
    )
    (net (code "79") (name "unconnected-(MUX-C15-Pad16)") (class "Default")
      (node (ref "MUX") (pin "16") (pinfunction "C15_16") (pintype "passive"))
    )
    (net (code "80") (name "unconnected-(U1-CLK-Pad1)") (class "Default")
      (node (ref "U1") (pin "1") (pinfunction "CLK_1") (pintype "passive+no_connect"))
    )
    (net (code "81") (name "unconnected-(U1-CMD-Pad37)") (class "Default")
      (node (ref "U1") (pin "37") (pinfunction "CMD_37") (pintype "passive+no_connect"))
    )
    (net (code "82") (name "unconnected-(U1-EN-Pad21)") (class "Default")
      (node (ref "U1") (pin "21") (pinfunction "EN_21") (pintype "passive"))
    )
    (net (code "83") (name "unconnected-(U1-P2-Pad5)") (class "Default")
      (node (ref "U1") (pin "5") (pinfunction "P2_5") (pintype "passive"))
    )
    (net (code "84") (name "unconnected-(U1-P5-Pad10)") (class "Default")
      (node (ref "U1") (pin "10") (pinfunction "P5_10") (pintype "passive"))
    )
    (net (code "85") (name "unconnected-(U1-P17-Pad9)") (class "Default")
      (node (ref "U1") (pin "9") (pinfunction "P17_9") (pintype "passive"))
    )
    (net (code "86") (name "unconnected-(U1-P26-Pad29)") (class "Default")
      (node (ref "U1") (pin "29") (pinfunction "P26_29") (pintype "passive"))
    )
    (net (code "87") (name "unconnected-(U1-P34-Pad24)") (class "Default")
      (node (ref "U1") (pin "24") (pinfunction "P34_24") (pintype "passive"))
    )
    (net (code "88") (name "unconnected-(U1-RX-Pad15)") (class "Default")
      (node (ref "U1") (pin "15") (pinfunction "RX_15") (pintype "passive+no_connect"))
    )
    (net (code "89") (name "unconnected-(U1-SD0-Pad2)") (class "Default")
      (node (ref "U1") (pin "2") (pinfunction "SD0_2") (pintype "passive+no_connect"))
    )
    (net (code "90") (name "unconnected-(U1-SD1-Pad3)") (class "Default")
      (node (ref "U1") (pin "3") (pinfunction "SD1_3") (pintype "passive+no_connect"))
    )
    (net (code "91") (name "unconnected-(U1-SD2-Pad35)") (class "Default")
      (node (ref "U1") (pin "35") (pinfunction "SD2_35") (pintype "passive+no_connect"))
    )
    (net (code "92") (name "unconnected-(U1-SD3-Pad36)") (class "Default")
      (node (ref "U1") (pin "36") (pinfunction "SD3_36") (pintype "passive+no_connect"))
    )
    (net (code "93") (name "unconnected-(U1-TX-Pad16)") (class "Default")
      (node (ref "U1") (pin "16") (pinfunction "TX_16") (pintype "passive+no_connect"))
    )
    (net (code "94") (name "unconnected-(U2-A0-Pad17)") (class "Default")
      (node (ref "U2") (pin "17") (pinfunction "A0_17") (pintype "passive"))
    )
    (net (code "95") (name "unconnected-(U2-A1-Pad18)") (class "Default")
      (node (ref "U2") (pin "18") (pinfunction "A1_18") (pintype "passive"))
    )
    (net (code "96") (name "unconnected-(U2-A2-Pad19)") (class "Default")
      (node (ref "U2") (pin "19") (pinfunction "A2_19") (pintype "passive"))
    )
    (net (code "97") (name "unconnected-(U2-A3-Pad20)") (class "Default")
      (node (ref "U2") (pin "20") (pinfunction "A3_20") (pintype "passive"))
    )
    (net (code "98") (name "unconnected-(U2-GND-Pad3)") (class "Default")
      (node (ref "U2") (pin "3") (pinfunction "GND_3") (pintype "passive"))
    )
    (net (code "99") (name "unconnected-(U2-GND-Pad4)") (class "Default")
      (node (ref "U2") (pin "4") (pinfunction "GND_4") (pintype "passive"))
    )
    (net (code "100") (name "unconnected-(U2-RAW-Pad24)") (class "Default")
      (node (ref "U2") (pin "24") (pinfunction "RAW_24") (pintype "passive"))
    )
    (net (code "101") (name "unconnected-(U2-RST-Pad22)") (class "Default")
      (node (ref "U2") (pin "22") (pinfunction "RST_22") (pintype "passive"))
    )
    (net (code "102") (name "unconnected-(U3-D2-Pad6)") (class "Default")
      (node (ref "U3") (pin "6") (pinfunction "D2_6") (pintype "passive"))
    )
    (net (code "103") (name "unconnected-(U3-D3-Pad7)") (class "Default")
      (node (ref "U3") (pin "7") (pinfunction "D3_7") (pintype "passive"))
    )
    (net (code "104") (name "unconnected-(U3-D4-Pad3)") (class "Default")
      (node (ref "U3") (pin "3") (pinfunction "D4_3") (pintype "passive"))
    )
    (net (code "105") (name "unconnected-(U3-D5-Pad10)") (class "Default")
      (node (ref "U3") (pin "10") (pinfunction "D5_10") (pintype "passive"))
    )
    (net (code "106") (name "unconnected-(U3-D6-Pad5)") (class "Default")
      (node (ref "U3") (pin "5") (pinfunction "D6_5") (pintype "passive"))
    )
    (net (code "107") (name "unconnected-(U3-D7-Pad8)") (class "Default")
      (node (ref "U3") (pin "8") (pinfunction "D7_8") (pintype "passive"))
    )
    (net (code "108") (name "unconnected-(U3-Dout-Pad24)") (class "Default")
      (node (ref "U3") (pin "24") (pinfunction "Dout_24") (pintype "passive"))
    )
    (net (code "109") (name "unconnected-(U4-HV1-Pad12)") (class "Default")
      (node (ref "U4") (pin "12") (pinfunction "HV1_12") (pintype "passive"))
    )
    (net (code "110") (name "unconnected-(U4-HV2-Pad11)") (class "Default")
      (node (ref "U4") (pin "11") (pinfunction "HV2_11") (pintype "passive"))
    )
    (net (code "111") (name "unconnected-(U4-LV1-Pad1)") (class "Default")
      (node (ref "U4") (pin "1") (pinfunction "LV1_1") (pintype "passive"))
    )
    (net (code "112") (name "unconnected-(U4-LV2-Pad2)") (class "Default")
      (node (ref "U4") (pin "2") (pinfunction "LV2_2") (pintype "passive"))
    )
  )
)
